# B135C.net
KiCad netlist of a schematic drawn in EAGLE
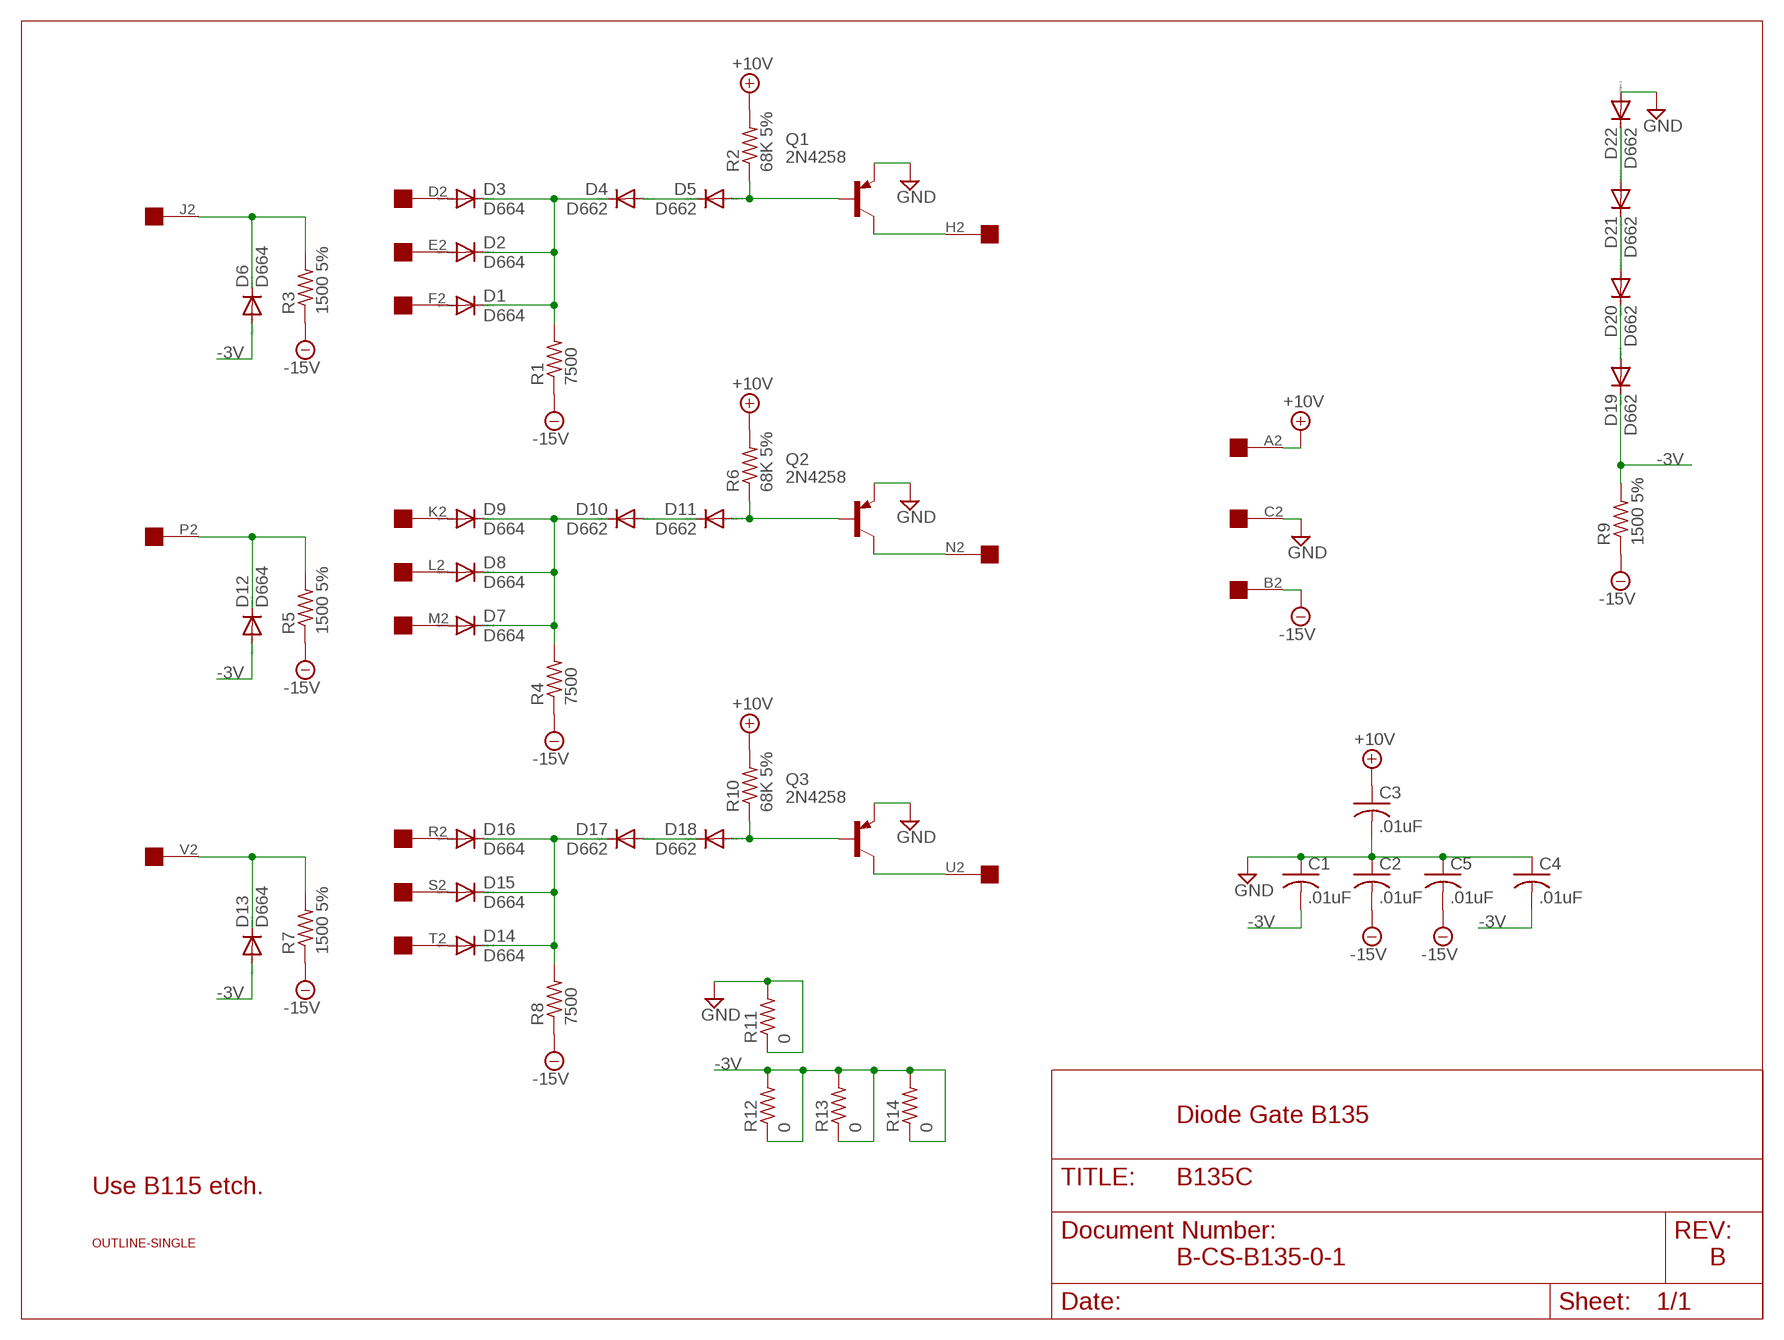
[diagram p0: schematic, sheet 1]

(export (version "E")
  (design (tool "Eeschema 10.0.6"))
  (components
    (comp (ref "C1")
      (value ".01uF")
      (footprint "eagle-import:C063-025X075")
      (libsource (lib "eagle-import") (part "C-US"))
    )
    (comp (ref "C2")
      (value ".01uF")
      (footprint "eagle-import:C063-025X075")
      (libsource (lib "eagle-import") (part "C-US"))
    )
    (comp (ref "C3")
      (value ".01uF")
      (footprint "eagle-import:C063-025X075")
      (libsource (lib "eagle-import") (part "C-US"))
    )
    (comp (ref "C4")
      (value ".01uF")
      (footprint "eagle-import:C063-025X075")
      (libsource (lib "eagle-import") (part "C-US"))
    )
    (comp (ref "C5")
      (value ".01uF")
      (footprint "eagle-import:C063-025X075")
      (libsource (lib "eagle-import") (part "C-US"))
    )
    (comp (ref "D1")
      (value "D664")
      (footprint "eagle-import:DO35-10")
      (libsource (lib "eagle-import") (part "DIODE-DO35-10"))
    )
    (comp (ref "D2")
      (value "D664")
      (footprint "eagle-import:DO35-10")
      (libsource (lib "eagle-import") (part "DIODE-DO35-10"))
    )
    (comp (ref "D3")
      (value "D664")
      (footprint "eagle-import:DO35-10")
      (libsource (lib "eagle-import") (part "DIODE-DO35-10"))
    )
    (comp (ref "D4")
      (value "D662")
      (footprint "eagle-import:DO35-10")
      (libsource (lib "eagle-import") (part "DIODE-DO35-10"))
    )
    (comp (ref "D5")
      (value "D662")
      (footprint "eagle-import:DO35-10")
      (libsource (lib "eagle-import") (part "DIODE-DO35-10"))
    )
    (comp (ref "D6")
      (value "D664")
      (footprint "eagle-import:DO35-10")
      (libsource (lib "eagle-import") (part "DIODE-DO35-10"))
    )
    (comp (ref "D7")
      (value "D664")
      (footprint "eagle-import:DO35-10")
      (libsource (lib "eagle-import") (part "DIODE-DO35-10"))
    )
    (comp (ref "D8")
      (value "D664")
      (footprint "eagle-import:DO35-10")
      (libsource (lib "eagle-import") (part "DIODE-DO35-10"))
    )
    (comp (ref "D9")
      (value "D664")
      (footprint "eagle-import:DO35-10")
      (libsource (lib "eagle-import") (part "DIODE-DO35-10"))
    )
    (comp (ref "D10")
      (value "D662")
      (footprint "eagle-import:DO35-10")
      (libsource (lib "eagle-import") (part "DIODE-DO35-10"))
    )
    (comp (ref "D11")
      (value "D662")
      (footprint "eagle-import:DO35-10")
      (libsource (lib "eagle-import") (part "DIODE-DO35-10"))
    )
    (comp (ref "D12")
      (value "D664")
      (footprint "eagle-import:DO35-10")
      (libsource (lib "eagle-import") (part "DIODE-DO35-10"))
    )
    (comp (ref "D13")
      (value "D664")
      (footprint "eagle-import:DO35-10")
      (libsource (lib "eagle-import") (part "DIODE-DO35-10"))
    )
    (comp (ref "D14")
      (value "D664")
      (footprint "eagle-import:DO35-10")
      (libsource (lib "eagle-import") (part "DIODE-DO35-10"))
    )
    (comp (ref "D15")
      (value "D664")
      (footprint "eagle-import:DO35-10")
      (libsource (lib "eagle-import") (part "DIODE-DO35-10"))
    )
    (comp (ref "D16")
      (value "D664")
      (footprint "eagle-import:DO35-10")
      (libsource (lib "eagle-import") (part "DIODE-DO35-10"))
    )
    (comp (ref "D17")
      (value "D662")
      (footprint "eagle-import:DO35-10")
      (libsource (lib "eagle-import") (part "DIODE-DO35-10"))
    )
    (comp (ref "D18")
      (value "D662")
      (footprint "eagle-import:DO35-10")
      (libsource (lib "eagle-import") (part "DIODE-DO35-10"))
    )
    (comp (ref "D19")
      (value "D662")
      (footprint "eagle-import:DO35-10")
      (libsource (lib "eagle-import") (part "DIODE-DO35-10"))
    )
    (comp (ref "D20")
      (value "D662")
      (footprint "eagle-import:DO35-10")
      (libsource (lib "eagle-import") (part "DIODE-DO35-10"))
    )
    (comp (ref "D21")
      (value "D662")
      (footprint "eagle-import:DO35-10")
      (libsource (lib "eagle-import") (part "DIODE-DO35-10"))
    )
    (comp (ref "D22")
      (value "D662")
      (footprint "eagle-import:DO35-10")
      (libsource (lib "eagle-import") (part "DIODE-DO35-10"))
    )
    (comp (ref "Q1")
      (value "2N4258")
      (footprint "eagle-import:TO5")
      (libsource (lib "eagle-import") (part "-PNP-TO5"))
    )
    (comp (ref "Q2")
      (value "2N4258")
      (footprint "eagle-import:TO5")
      (libsource (lib "eagle-import") (part "-PNP-TO5"))
    )
    (comp (ref "Q3")
      (value "2N4258")
      (footprint "eagle-import:TO5")
      (libsource (lib "eagle-import") (part "-PNP-TO5"))
    )
    (comp (ref "R1")
      (value "7500")
      (footprint "eagle-import:0207_10")
      (libsource (lib "eagle-import") (part "R-US_0207/10"))
    )
    (comp (ref "R2")
      (value "68K 5%")
      (footprint "eagle-import:0207_10")
      (libsource (lib "eagle-import") (part "R-US_0207/10"))
    )
    (comp (ref "R3")
      (value "1500 5%")
      (footprint "eagle-import:0207_10")
      (libsource (lib "eagle-import") (part "R-US_0207/10"))
    )
    (comp (ref "R4")
      (value "7500")
      (footprint "eagle-import:0207_10")
      (libsource (lib "eagle-import") (part "R-US_0207/10"))
    )
    (comp (ref "R5")
      (value "1500 5%")
      (footprint "eagle-import:0207_10")
      (libsource (lib "eagle-import") (part "R-US_0207/10"))
    )
    (comp (ref "R6")
      (value "68K 5%")
      (footprint "eagle-import:0207_10")
      (libsource (lib "eagle-import") (part "R-US_0207/10"))
    )
    (comp (ref "R7")
      (value "1500 5%")
      (footprint "eagle-import:0207_10")
      (libsource (lib "eagle-import") (part "R-US_0207/10"))
    )
    (comp (ref "R8")
      (value "7500")
      (footprint "eagle-import:0207_10")
      (libsource (lib "eagle-import") (part "R-US_0207/10"))
    )
    (comp (ref "R9")
      (value "1500 5%")
      (footprint "eagle-import:0207_10")
      (libsource (lib "eagle-import") (part "R-US_0207/10"))
    )
    (comp (ref "R10")
      (value "68K 5%")
      (footprint "eagle-import:0207_10")
      (libsource (lib "eagle-import") (part "R-US_0207/10"))
    )
    (comp (ref "R11")
      (value "0")
      (footprint "eagle-import:0207_10")
      (libsource (lib "eagle-import") (part "R-US_0207/10"))
    )
    (comp (ref "R12")
      (value "0")
      (footprint "eagle-import:0207_10")
      (libsource (lib "eagle-import") (part "R-US_0207/10"))
    )
    (comp (ref "R13")
      (value "0")
      (footprint "eagle-import:0207_10")
      (libsource (lib "eagle-import") (part "R-US_0207/10"))
    )
    (comp (ref "R14")
      (value "0")
      (footprint "eagle-import:0207_10")
      (libsource (lib "eagle-import") (part "R-US_0207/10"))
    )
    (comp (ref "U$1")
      (value "OUTLINE-SINGLE")
      (footprint "eagle-import:SINGLE")
      (libsource (lib "eagle-import") (part "OUTLINE-SINGLE"))
    )
    (comp (ref "U$2")
      (value "EDGE-1")
      (footprint "eagle-import:EDGE-CON1")
      (libsource (lib "eagle-import") (part "EDGE-1"))
    )
  )
  (nets
    (net (code "1") (name "+10V") (class "Default")
      (node (ref "C3") (pin "1") (pinfunction "1_1") (pintype "passive"))
      (node (ref "R10") (pin "2") (pinfunction "2_2") (pintype "passive"))
      (node (ref "R2") (pin "2") (pinfunction "2_2") (pintype "passive"))
      (node (ref "R6") (pin "2") (pinfunction "2_2") (pintype "passive"))
      (node (ref "U$2") (pin "A2") (pinfunction "1_A2") (pintype "bidirectional"))
    )
    (net (code "2") (name "-15V") (class "Default")
      (node (ref "C2") (pin "2") (pinfunction "2_2") (pintype "passive"))
      (node (ref "C5") (pin "2") (pinfunction "2_2") (pintype "passive"))
      (node (ref "R1") (pin "1") (pinfunction "1_1") (pintype "passive"))
      (node (ref "R3") (pin "1") (pinfunction "1_1") (pintype "passive"))
      (node (ref "R4") (pin "1") (pinfunction "1_1") (pintype "passive"))
      (node (ref "R5") (pin "1") (pinfunction "1_1") (pintype "passive"))
      (node (ref "R7") (pin "1") (pinfunction "1_1") (pintype "passive"))
      (node (ref "R8") (pin "1") (pinfunction "1_1") (pintype "passive"))
      (node (ref "R9") (pin "1") (pinfunction "1_1") (pintype "passive"))
      (node (ref "U$2") (pin "B2") (pinfunction "1_B2") (pintype "bidirectional"))
    )
    (net (code "3") (name "/-3V") (class "Default")
      (node (ref "C1") (pin "2") (pinfunction "2_2") (pintype "passive"))
      (node (ref "C4") (pin "2") (pinfunction "2_2") (pintype "passive"))
      (node (ref "D12") (pin "A") (pinfunction "A_A") (pintype "passive"))
      (node (ref "D13") (pin "A") (pinfunction "A_A") (pintype "passive"))
      (node (ref "D19") (pin "C") (pinfunction "C_C") (pintype "passive"))
      (node (ref "D6") (pin "A") (pinfunction "A_A") (pintype "passive"))
      (node (ref "R12") (pin "1") (pinfunction "1_1") (pintype "passive"))
      (node (ref "R12") (pin "2") (pinfunction "2_2") (pintype "passive"))
      (node (ref "R13") (pin "1") (pinfunction "1_1") (pintype "passive"))
      (node (ref "R13") (pin "2") (pinfunction "2_2") (pintype "passive"))
      (node (ref "R14") (pin "1") (pinfunction "1_1") (pintype "passive"))
      (node (ref "R14") (pin "2") (pinfunction "2_2") (pintype "passive"))
      (node (ref "R9") (pin "2") (pinfunction "2_2") (pintype "passive"))
    )
    (net (code "4") (name "GND") (class "Default")
      (node (ref "C1") (pin "1") (pinfunction "1_1") (pintype "passive"))
      (node (ref "C2") (pin "1") (pinfunction "1_1") (pintype "passive"))
      (node (ref "C3") (pin "2") (pinfunction "2_2") (pintype "passive"))
      (node (ref "C4") (pin "1") (pinfunction "1_1") (pintype "passive"))
      (node (ref "C5") (pin "1") (pinfunction "1_1") (pintype "passive"))
      (node (ref "D22") (pin "A") (pinfunction "A_A") (pintype "passive"))
      (node (ref "Q1") (pin "1") (pinfunction "E_1") (pintype "passive"))
      (node (ref "Q2") (pin "1") (pinfunction "E_1") (pintype "passive"))
      (node (ref "Q3") (pin "1") (pinfunction "E_1") (pintype "passive"))
      (node (ref "R11") (pin "1") (pinfunction "1_1") (pintype "passive"))
      (node (ref "R11") (pin "2") (pinfunction "2_2") (pintype "passive"))
      (node (ref "U$2") (pin "C2") (pinfunction "1_C2") (pintype "bidirectional"))
    )
    (net (code "5") (name "Net-(D1-PadC)") (class "Default")
      (node (ref "D1") (pin "C") (pinfunction "C_C") (pintype "passive"))
      (node (ref "D2") (pin "C") (pinfunction "C_C") (pintype "passive"))
      (node (ref "D3") (pin "C") (pinfunction "C_C") (pintype "passive"))
      (node (ref "D4") (pin "C") (pinfunction "C_C") (pintype "passive"))
      (node (ref "R1") (pin "2") (pinfunction "2_2") (pintype "passive"))
    )
    (net (code "6") (name "Net-(D4-PadA)") (class "Default")
      (node (ref "D4") (pin "A") (pinfunction "A_A") (pintype "passive"))
      (node (ref "D5") (pin "C") (pinfunction "C_C") (pintype "passive"))
    )
    (net (code "7") (name "Net-(D10-PadA)") (class "Default")
      (node (ref "D10") (pin "A") (pinfunction "A_A") (pintype "passive"))
      (node (ref "D11") (pin "C") (pinfunction "C_C") (pintype "passive"))
    )
    (net (code "8") (name "Net-(D10-PadC)") (class "Default")
      (node (ref "D10") (pin "C") (pinfunction "C_C") (pintype "passive"))
      (node (ref "D7") (pin "C") (pinfunction "C_C") (pintype "passive"))
      (node (ref "D8") (pin "C") (pinfunction "C_C") (pintype "passive"))
      (node (ref "D9") (pin "C") (pinfunction "C_C") (pintype "passive"))
      (node (ref "R4") (pin "2") (pinfunction "2_2") (pintype "passive"))
    )
    (net (code "9") (name "Net-(D14-PadC)") (class "Default")
      (node (ref "D14") (pin "C") (pinfunction "C_C") (pintype "passive"))
      (node (ref "D15") (pin "C") (pinfunction "C_C") (pintype "passive"))
      (node (ref "D16") (pin "C") (pinfunction "C_C") (pintype "passive"))
      (node (ref "D17") (pin "C") (pinfunction "C_C") (pintype "passive"))
      (node (ref "R8") (pin "2") (pinfunction "2_2") (pintype "passive"))
    )
    (net (code "10") (name "Net-(D17-PadA)") (class "Default")
      (node (ref "D17") (pin "A") (pinfunction "A_A") (pintype "passive"))
      (node (ref "D18") (pin "C") (pinfunction "C_C") (pintype "passive"))
    )
    (net (code "11") (name "Net-(D19-PadA)") (class "Default")
      (node (ref "D19") (pin "A") (pinfunction "A_A") (pintype "passive"))
      (node (ref "D20") (pin "C") (pinfunction "C_C") (pintype "passive"))
    )
    (net (code "12") (name "Net-(D20-PadA)") (class "Default")
      (node (ref "D20") (pin "A") (pinfunction "A_A") (pintype "passive"))
      (node (ref "D21") (pin "C") (pinfunction "C_C") (pintype "passive"))
    )
    (net (code "13") (name "Net-(D21-PadA)") (class "Default")
      (node (ref "D21") (pin "A") (pinfunction "A_A") (pintype "passive"))
      (node (ref "D22") (pin "C") (pinfunction "C_C") (pintype "passive"))
    )
    (net (code "14") (name "Net-(Q1-B)") (class "Default")
      (node (ref "D5") (pin "A") (pinfunction "A_A") (pintype "passive"))
      (node (ref "Q1") (pin "2") (pinfunction "B_2") (pintype "passive"))
      (node (ref "R2") (pin "1") (pinfunction "1_1") (pintype "passive"))
    )
    (net (code "15") (name "Net-(Q1-C)") (class "Default")
      (node (ref "Q1") (pin "3") (pinfunction "C_3") (pintype "passive"))
      (node (ref "U$2") (pin "H2") (pinfunction "1_H2") (pintype "bidirectional"))
    )
    (net (code "16") (name "Net-(Q2-B)") (class "Default")
      (node (ref "D11") (pin "A") (pinfunction "A_A") (pintype "passive"))
      (node (ref "Q2") (pin "2") (pinfunction "B_2") (pintype "passive"))
      (node (ref "R6") (pin "1") (pinfunction "1_1") (pintype "passive"))
    )
    (net (code "17") (name "Net-(Q2-C)") (class "Default")
      (node (ref "Q2") (pin "3") (pinfunction "C_3") (pintype "passive"))
      (node (ref "U$2") (pin "N2") (pinfunction "1_N2") (pintype "bidirectional"))
    )
    (net (code "18") (name "Net-(Q3-B)") (class "Default")
      (node (ref "D18") (pin "A") (pinfunction "A_A") (pintype "passive"))
      (node (ref "Q3") (pin "2") (pinfunction "B_2") (pintype "passive"))
      (node (ref "R10") (pin "1") (pinfunction "1_1") (pintype "passive"))
    )
    (net (code "19") (name "Net-(Q3-C)") (class "Default")
      (node (ref "Q3") (pin "3") (pinfunction "C_3") (pintype "passive"))
      (node (ref "U$2") (pin "U2") (pinfunction "1_U2") (pintype "bidirectional"))
    )
    (net (code "20") (name "Net-(U$2D-1)") (class "Default")
      (node (ref "D3") (pin "A") (pinfunction "A_A") (pintype "passive"))
      (node (ref "U$2") (pin "D2") (pinfunction "1_D2") (pintype "bidirectional"))
    )
    (net (code "21") (name "Net-(U$2E-1)") (class "Default")
      (node (ref "D2") (pin "A") (pinfunction "A_A") (pintype "passive"))
      (node (ref "U$2") (pin "E2") (pinfunction "1_E2") (pintype "bidirectional"))
    )
    (net (code "22") (name "Net-(U$2F-1)") (class "Default")
      (node (ref "D1") (pin "A") (pinfunction "A_A") (pintype "passive"))
      (node (ref "U$2") (pin "F2") (pinfunction "1_F2") (pintype "bidirectional"))
    )
    (net (code "23") (name "Net-(U$2H-1)") (class "Default")
      (node (ref "D6") (pin "C") (pinfunction "C_C") (pintype "passive"))
      (node (ref "R3") (pin "2") (pinfunction "2_2") (pintype "passive"))
      (node (ref "U$2") (pin "J2") (pinfunction "1_J2") (pintype "bidirectional"))
    )
    (net (code "24") (name "Net-(U$2I-1)") (class "Default")
      (node (ref "D9") (pin "A") (pinfunction "A_A") (pintype "passive"))
      (node (ref "U$2") (pin "K2") (pinfunction "1_K2") (pintype "bidirectional"))
    )
    (net (code "25") (name "Net-(U$2J-1)") (class "Default")
      (node (ref "D8") (pin "A") (pinfunction "A_A") (pintype "passive"))
      (node (ref "U$2") (pin "L2") (pinfunction "1_L2") (pintype "bidirectional"))
    )
    (net (code "26") (name "Net-(U$2K-1)") (class "Default")
      (node (ref "D7") (pin "A") (pinfunction "A_A") (pintype "passive"))
      (node (ref "U$2") (pin "M2") (pinfunction "1_M2") (pintype "bidirectional"))
    )
    (net (code "27") (name "Net-(U$2M-1)") (class "Default")
      (node (ref "D12") (pin "C") (pinfunction "C_C") (pintype "passive"))
      (node (ref "R5") (pin "2") (pinfunction "2_2") (pintype "passive"))
      (node (ref "U$2") (pin "P2") (pinfunction "1_P2") (pintype "bidirectional"))
    )
    (net (code "28") (name "Net-(U$2N-1)") (class "Default")
      (node (ref "D16") (pin "A") (pinfunction "A_A") (pintype "passive"))
      (node (ref "U$2") (pin "R2") (pinfunction "1_R2") (pintype "bidirectional"))
    )
    (net (code "29") (name "Net-(U$2O-1)") (class "Default")
      (node (ref "D15") (pin "A") (pinfunction "A_A") (pintype "passive"))
      (node (ref "U$2") (pin "S2") (pinfunction "1_S2") (pintype "bidirectional"))
    )
    (net (code "30") (name "Net-(U$2P-1)") (class "Default")
      (node (ref "D14") (pin "A") (pinfunction "A_A") (pintype "passive"))
      (node (ref "U$2") (pin "T2") (pinfunction "1_T2") (pintype "bidirectional"))
    )
    (net (code "31") (name "Net-(U$2R-1)") (class "Default")
      (node (ref "D13") (pin "C") (pinfunction "C_C") (pintype "passive"))
      (node (ref "R7") (pin "2") (pinfunction "2_2") (pintype "passive"))
      (node (ref "U$2") (pin "V2") (pinfunction "1_V2") (pintype "bidirectional"))
    )
  )
)
